# COMUNICATE_CON.net
KiCad netlist of a schematic drawn in Altium Designer
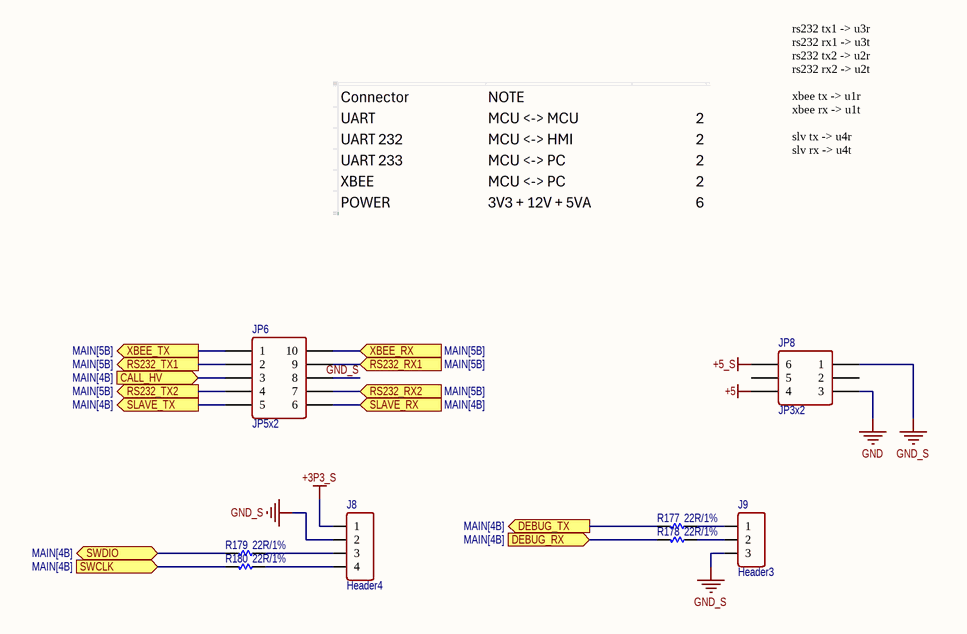
[diagram p0: COMUNICATE_CON.SchDoc]

(export (version "E")
  (design (tool "Eeschema 10.0.6"))
  (components
    (comp (ref "J8")
      (value "Header4")
      (footprint "XH2.54-4-DIP")
      (description "Connector 4")
      (fields
        (field (name "MANUFACTURER") "Würth Elektronik eiSos GmbH")
        (field (name "PARTNO") "613002143121")
        (field (name "CREATED BY") "Karrer Zheng")
      )
      (libsource (lib "Library") (part "Header4"))
    )
    (comp (ref "J9")
      (value "Header3")
      (footprint "XH2.54-3-DIP")
      (description "Connector 3")
      (fields
        (field (name "MANUFACTURER") "Würth Elektronik eiSos GmbH")
        (field (name "PARTNO") "613002143121")
        (field (name "CREATED BY") "Karrer Zheng")
      )
      (libsource (lib "Library") (part "Header3"))
    )
    (comp (ref "JP6")
      (value "JP5x2")
      (footprint "JP5-C2T")
      (description "CONN RCPT 10POS 0.1 GOLD PCB")
      (fields
        (field (name "MANUFACTURER") "Würth Elektronik eiSos GmbH")
        (field (name "PARTNO") "61301021821")
        (field (name "CREATED BY") "Karrer Zheng")
      )
      (libsource (lib "Library") (part "JP5x2"))
    )
    (comp (ref "JP8")
      (value "JP3x2")
      (footprint "JP3-C2T")
      (description "CONN RCPT 6POS 0.1 GOLD PCB")
      (fields
        (field (name "MANUFACTURER") "Würth Elektronik eiSos GmbH")
        (field (name "PARTNO") "61300621821")
        (field (name "CREATED BY") "Karrer Zheng")
      )
      (libsource (lib "Library") (part "JP3x2"))
    )
    (comp (ref "R177")
      (value "22R/1%")
      (footprint "RES-SMD-0603")
      (description "RES SMD 22 OHM 1% 1/10W 0603")
      (libsource (lib "Library") (part "Res-SMD"))
    )
    (comp (ref "R178")
      (value "22R/1%")
      (footprint "RES-SMD-0603")
      (description "RES SMD 22 OHM 1% 1/10W 0603")
      (libsource (lib "Library") (part "Res-SMD"))
    )
    (comp (ref "R179")
      (value "22R/1%")
      (footprint "RES-SMD-0603")
      (description "RES SMD 22 OHM 1% 1/10W 0603")
      (libsource (lib "Library") (part "Res-SMD"))
    )
    (comp (ref "R180")
      (value "22R/1%")
      (footprint "RES-SMD-0603")
      (description "RES SMD 22 OHM 1% 1/10W 0603")
      (libsource (lib "Library") (part "Res-SMD"))
    )
  )
  (nets
    (net (code "1") (name "+3P3_S") (class "Default")
      (node (ref "J8") (pin "1") (pinfunction "1_1") (pintype "passive"))
    )
    (net (code "2") (name "+5") (class "Default")
      (node (ref "JP8") (pin "4") (pinfunction "4_4") (pintype "passive"))
    )
    (net (code "3") (name "+5_S") (class "Default")
      (node (ref "JP8") (pin "6") (pinfunction "6_6") (pintype "passive"))
    )
    (net (code "4") (name "/CALL_HV") (class "Default")
      (node (ref "JP6") (pin "3") (pinfunction "3_3") (pintype "passive"))
    )
    (net (code "5") (name "/DEBUG_RX") (class "Default")
      (node (ref "R178") (pin "2") (pinfunction "2_2") (pintype "passive"))
    )
    (net (code "6") (name "/DEBUG_TX") (class "Default")
      (node (ref "R177") (pin "2") (pinfunction "2_2") (pintype "passive"))
    )
    (net (code "7") (name "/RS232_RX1") (class "Default")
      (node (ref "JP6") (pin "9") (pinfunction "9_9") (pintype "passive"))
    )
    (net (code "8") (name "/RS232_RX2") (class "Default")
      (node (ref "JP6") (pin "7") (pinfunction "7_7") (pintype "passive"))
    )
    (net (code "9") (name "/RS232_TX1") (class "Default")
      (node (ref "JP6") (pin "2") (pinfunction "2_2") (pintype "passive"))
    )
    (net (code "10") (name "/RS232_TX2") (class "Default")
      (node (ref "JP6") (pin "4") (pinfunction "4_4") (pintype "passive"))
    )
    (net (code "11") (name "/SLAVE_RX") (class "Default")
      (node (ref "JP6") (pin "6") (pinfunction "6_6") (pintype "passive"))
    )
    (net (code "12") (name "/SLAVE_TX") (class "Default")
      (node (ref "JP6") (pin "5") (pinfunction "5_5") (pintype "passive"))
    )
    (net (code "13") (name "/SWCLK") (class "Default")
      (node (ref "R180") (pin "2") (pinfunction "2_2") (pintype "passive"))
    )
    (net (code "14") (name "/SWDIO") (class "Default")
      (node (ref "R179") (pin "2") (pinfunction "2_2") (pintype "passive"))
    )
    (net (code "15") (name "/XBEE_RX") (class "Default")
      (node (ref "JP6") (pin "10") (pinfunction "10_10") (pintype "passive"))
    )
    (net (code "16") (name "/XBEE_TX") (class "Default")
      (node (ref "JP6") (pin "1") (pinfunction "1_1") (pintype "passive"))
    )
    (net (code "17") (name "GND") (class "Default")
      (node (ref "JP8") (pin "3") (pinfunction "3_3") (pintype "passive"))
    )
    (net (code "18") (name "GND_S") (class "Default")
      (node (ref "J8") (pin "2") (pinfunction "2_2") (pintype "passive"))
      (node (ref "J9") (pin "3") (pinfunction "3_3") (pintype "passive"))
      (node (ref "JP6") (pin "8") (pinfunction "8_8") (pintype "passive"))
      (node (ref "JP8") (pin "1") (pinfunction "1_1") (pintype "passive"))
    )
    (net (code "19") (name "Net-(J8-Pad3)") (class "Default")
      (node (ref "J8") (pin "3") (pinfunction "3_3") (pintype "passive"))
      (node (ref "R179") (pin "1") (pinfunction "1_1") (pintype "passive"))
    )
    (net (code "20") (name "Net-(J8-Pad4)") (class "Default")
      (node (ref "J8") (pin "4") (pinfunction "4_4") (pintype "passive"))
      (node (ref "R180") (pin "1") (pinfunction "1_1") (pintype "passive"))
    )
    (net (code "21") (name "Net-(J9-Pad1)") (class "Default")
      (node (ref "J9") (pin "1") (pinfunction "1_1") (pintype "passive"))
      (node (ref "R177") (pin "1") (pinfunction "1_1") (pintype "passive"))
    )
    (net (code "22") (name "Net-(J9-Pad2)") (class "Default")
      (node (ref "J9") (pin "2") (pinfunction "2_2") (pintype "passive"))
      (node (ref "R178") (pin "1") (pinfunction "1_1") (pintype "passive"))
    )
    (net (code "23") (name "unconnected-(JP8-Pad2)") (class "Default")
      (node (ref "JP8") (pin "2") (pinfunction "2_2") (pintype "passive"))
    )
    (net (code "24") (name "unconnected-(JP8-Pad5)") (class "Default")
      (node (ref "JP8") (pin "5") (pinfunction "5_5") (pintype "passive"))
    )
  )
)
